# HV-Measurement.net
KiCad netlist of a schematic drawn in Altium Designer
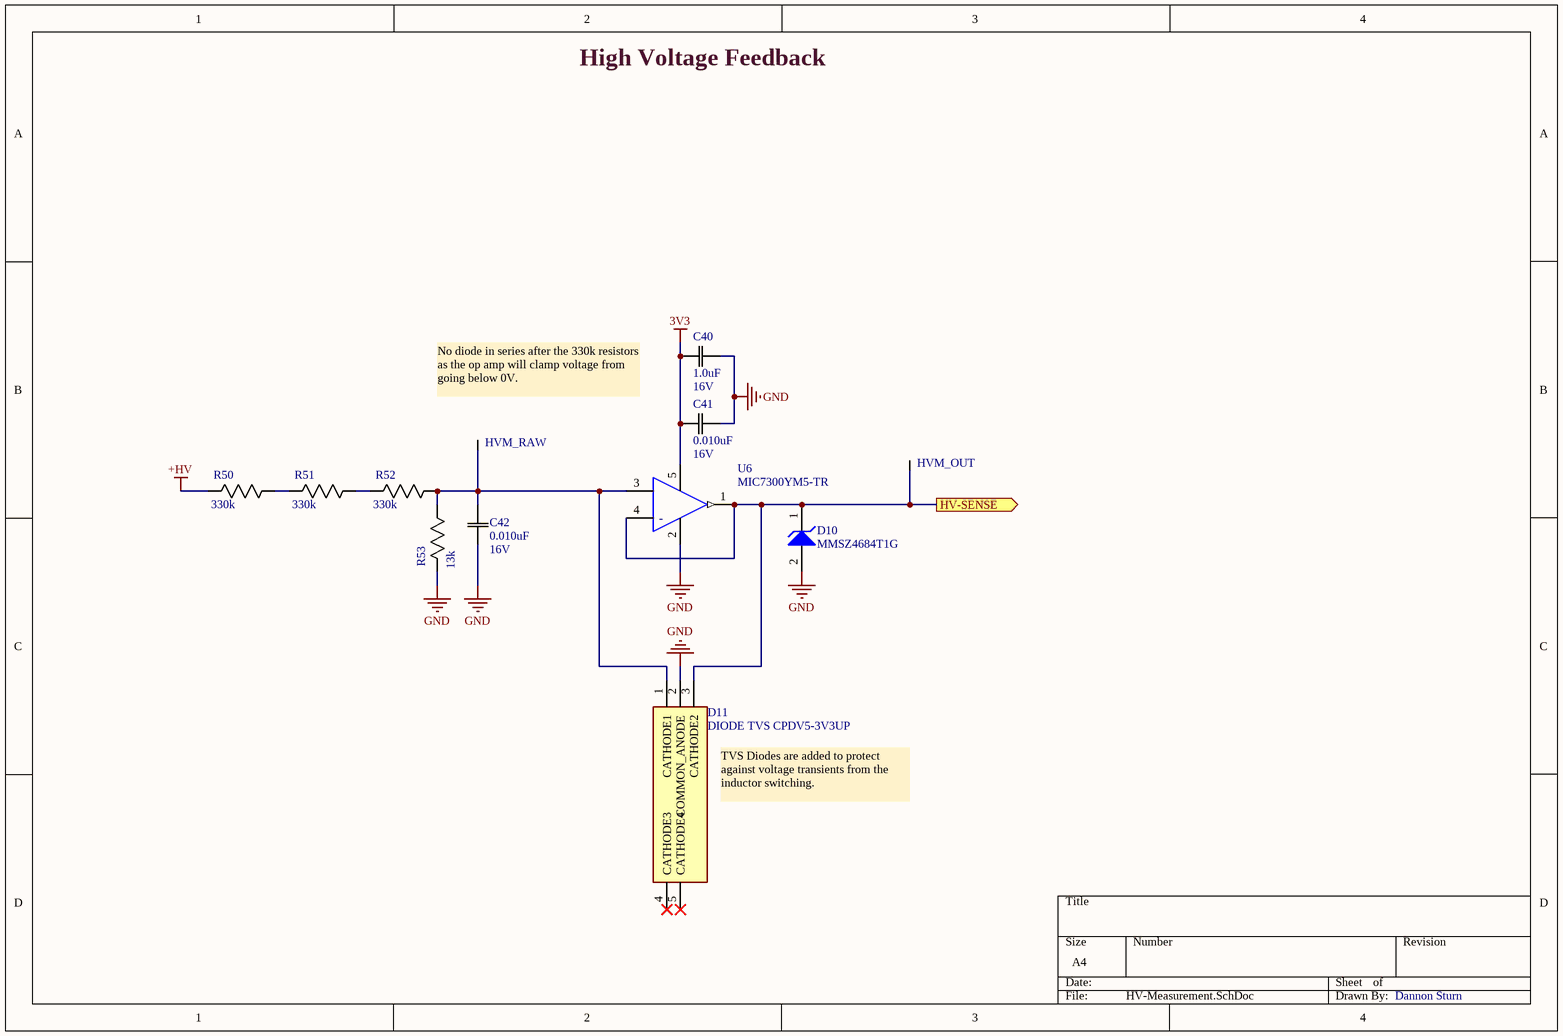
[diagram p0: HV-Measurement.SchDoc]

(export (version "E")
  (design (tool "Eeschema 10.0.6"))
  (components
    (comp (ref "C40")
      (value "1.0uF")
      (footprint "0805")
      (description "CAP CER 1.0UF 16V X5R 0603/0805")
      (fields (field (name "TOLERANCE") "10%") (field (name "RATING") "16V"))
      (libsource (lib "AltiumLibraries") (part "CAP 1.0uF 16V"))
    )
    (comp (ref "C41")
      (value "0.010uF")
      (footprint "0805")
      (description "CAP CER 0.010UF 16V X5R 0603/0805")
      (fields (field (name "TOLERANCE") "10%") (field (name "RATING") "16V"))
      (libsource (lib "AltiumLibraries") (part "CAP 0.010uF 16V"))
    )
    (comp (ref "C42")
      (value "0.010uF")
      (footprint "0805")
      (description "CAP CER 0.010UF 16V X5R 0603/0805")
      (fields (field (name "TOLERANCE") "10%") (field (name "RATING") "16V"))
      (libsource (lib "AltiumLibraries") (part "CAP 0.010uF 16V"))
    )
    (comp (ref "D10")
      (value "MMSZ4684T1G")
      (footprint "ONSC-SOD-123-2-425-04_V")
      (description "Zener 3V3 Voltage Regulator, 500 mW, 2-Pin SOD-123, Pb-Free, Tape and Reel")
      (fields (field (name "MANUFACTURER") "On Semiconductor"))
      (libsource (lib "AltiumLibraries") (part "DIODE ZENER 3.3 500mW"))
    )
    (comp (ref "D11")
      (value "DIODE TVS CPDV5-3V3UP")
      (footprint "SOT65P230X110-5N")
      (description "TVS Diode Bidirectional Vbr = 3.5V, Working Voltage = 3.3V")
      (fields
        (field (name "MANUFACTURER_PART_NUMBER") "CPDV5-3V3UP")
        (field (name "MOUSER PART NUMBER") "750-CPDV5-3V3UP")
      )
      (libsource (lib "AltiumLibraries") (part "DIODE TVS CPDV5-3V3UP"))
    )
    (comp (ref "HVM_OUT")
      (value "Test Point (Via)")
      (footprint "TP")
      (libsource (lib "AltiumLibraries") (part "Test Point (Via)"))
    )
    (comp (ref "HVM_RAW")
      (value "Test Point (Via)")
      (footprint "TP")
      (libsource (lib "AltiumLibraries") (part "Test Point (Via)"))
    )
    (comp (ref "R50")
      (value "330k")
      (footprint "0805")
      (description "RES SMD 330K OHM 5% 1/8W 0805")
      (fields (field (name "TOLERANCE") "5%"))
      (libsource (lib "AltiumLibraries") (part "RES 330k 1/8W - 5%"))
    )
    (comp (ref "R51")
      (value "330k")
      (footprint "0805")
      (description "RES SMD 330K OHM 5% 1/8W 0805")
      (fields (field (name "TOLERANCE") "5%"))
      (libsource (lib "") (part "RES 330k 1/8W - 5%_1"))
    )
    (comp (ref "R52")
      (value "330k")
      (footprint "0805")
      (description "RES SMD 330K OHM 5% 1/8W 0805")
      (fields (field (name "TOLERANCE") "5%"))
      (libsource (lib "") (part "RES 330k 1/8W - 5%_1"))
    )
    (comp (ref "R53")
      (value "13k")
      (footprint "0805")
      (description "RES SMD 13K OHM 5% 1/8W 0805")
      (fields (field (name "TOLERANCE") "5%"))
      (libsource (lib "AltiumLibraries") (part "RES 13k 1/8W"))
    )
    (comp (ref "U6")
      (value "MIC7300YM5-TR")
      (footprint "FP-SOT23-5LD-PL-1-IPC_A")
      (description "IC OPAMP GP 1 CIRCUIT SOT23-5")
      (fields
        (field (name "OCTOPART") "https://octopart.com/mic7300ym5-tr-microchip-66803593")
        (field (name "MANUFACTURER") "Microchip")
      )
      (libsource (lib "AltiumLibraries") (part "OP AMP MIC7300YM5-TR"))
    )
  )
  (nets
    (net (code "1") (name "+HV") (class "Default")
      (node (ref "R50") (pin "2") (pinfunction "R2_2") (pintype "passive"))
    )
    (net (code "2") (name "/HV-SENSE") (class "Default")
      (node (ref "D10") (pin "1") (pinfunction "K_1") (pintype "passive"))
      (node (ref "D11") (pin "3") (pinfunction "CATHODE2_3") (pintype "passive"))
      (node (ref "HVM_OUT") (pin "1") (pinfunction "1_1") (pintype "passive"))
      (node (ref "U6") (pin "1") (pinfunction "OUT_1") (pintype "output"))
      (node (ref "U6") (pin "4") (pinfunction "IN-_4") (pintype "tri_state"))
    )
    (net (code "3") (name "3V3") (class "Default")
      (node (ref "C40") (pin "2") (pinfunction "C2_2") (pintype "passive"))
      (node (ref "C41") (pin "1") (pinfunction "C1_1") (pintype "passive"))
      (node (ref "U6") (pin "5") (pinfunction "V+_5") (pintype "power_in"))
    )
    (net (code "4") (name "GND") (class "Default")
      (node (ref "C40") (pin "1") (pinfunction "C1_1") (pintype "passive"))
      (node (ref "C41") (pin "2") (pinfunction "C2_2") (pintype "passive"))
      (node (ref "C42") (pin "1") (pinfunction "C1_1") (pintype "passive"))
      (node (ref "D10") (pin "2") (pinfunction "A_2") (pintype "passive"))
      (node (ref "D11") (pin "2") (pinfunction "COMMON_ANODE_2") (pintype "passive"))
      (node (ref "R53") (pin "2") (pinfunction "R2_2") (pintype "passive"))
      (node (ref "U6") (pin "2") (pinfunction "V-_2") (pintype "power_in"))
    )
    (net (code "5") (name "Net-(C42-C2)") (class "Default")
      (node (ref "C42") (pin "2") (pinfunction "C2_2") (pintype "passive"))
      (node (ref "D11") (pin "1") (pinfunction "CATHODE1_1") (pintype "passive"))
      (node (ref "HVM_RAW") (pin "1") (pinfunction "1_1") (pintype "passive"))
      (node (ref "R52") (pin "1") (pinfunction "R1_1") (pintype "passive"))
      (node (ref "R53") (pin "1") (pinfunction "R1_1") (pintype "passive"))
      (node (ref "U6") (pin "3") (pinfunction "IN+_3") (pintype "tri_state"))
    )
    (net (code "6") (name "Net-(R50-R1)") (class "Default")
      (node (ref "R50") (pin "1") (pinfunction "R1_1") (pintype "passive"))
      (node (ref "R51") (pin "2") (pinfunction "R2_2") (pintype "passive"))
    )
    (net (code "7") (name "Net-(R51-R1)") (class "Default")
      (node (ref "R51") (pin "1") (pinfunction "R1_1") (pintype "passive"))
      (node (ref "R52") (pin "2") (pinfunction "R2_2") (pintype "passive"))
    )
    (net (code "8") (name "unconnected-(D11-CATHODE3-Pad4)") (class "Default")
      (node (ref "D11") (pin "4") (pinfunction "CATHODE3_4") (pintype "passive+no_connect"))
    )
    (net (code "9") (name "unconnected-(D11-CATHODE4-Pad5)") (class "Default")
      (node (ref "D11") (pin "5") (pinfunction "CATHODE4_5") (pintype "passive+no_connect"))
    )
  )
)
